# Main_autotest.net
KiCad netlist of a schematic drawn in EAGLE
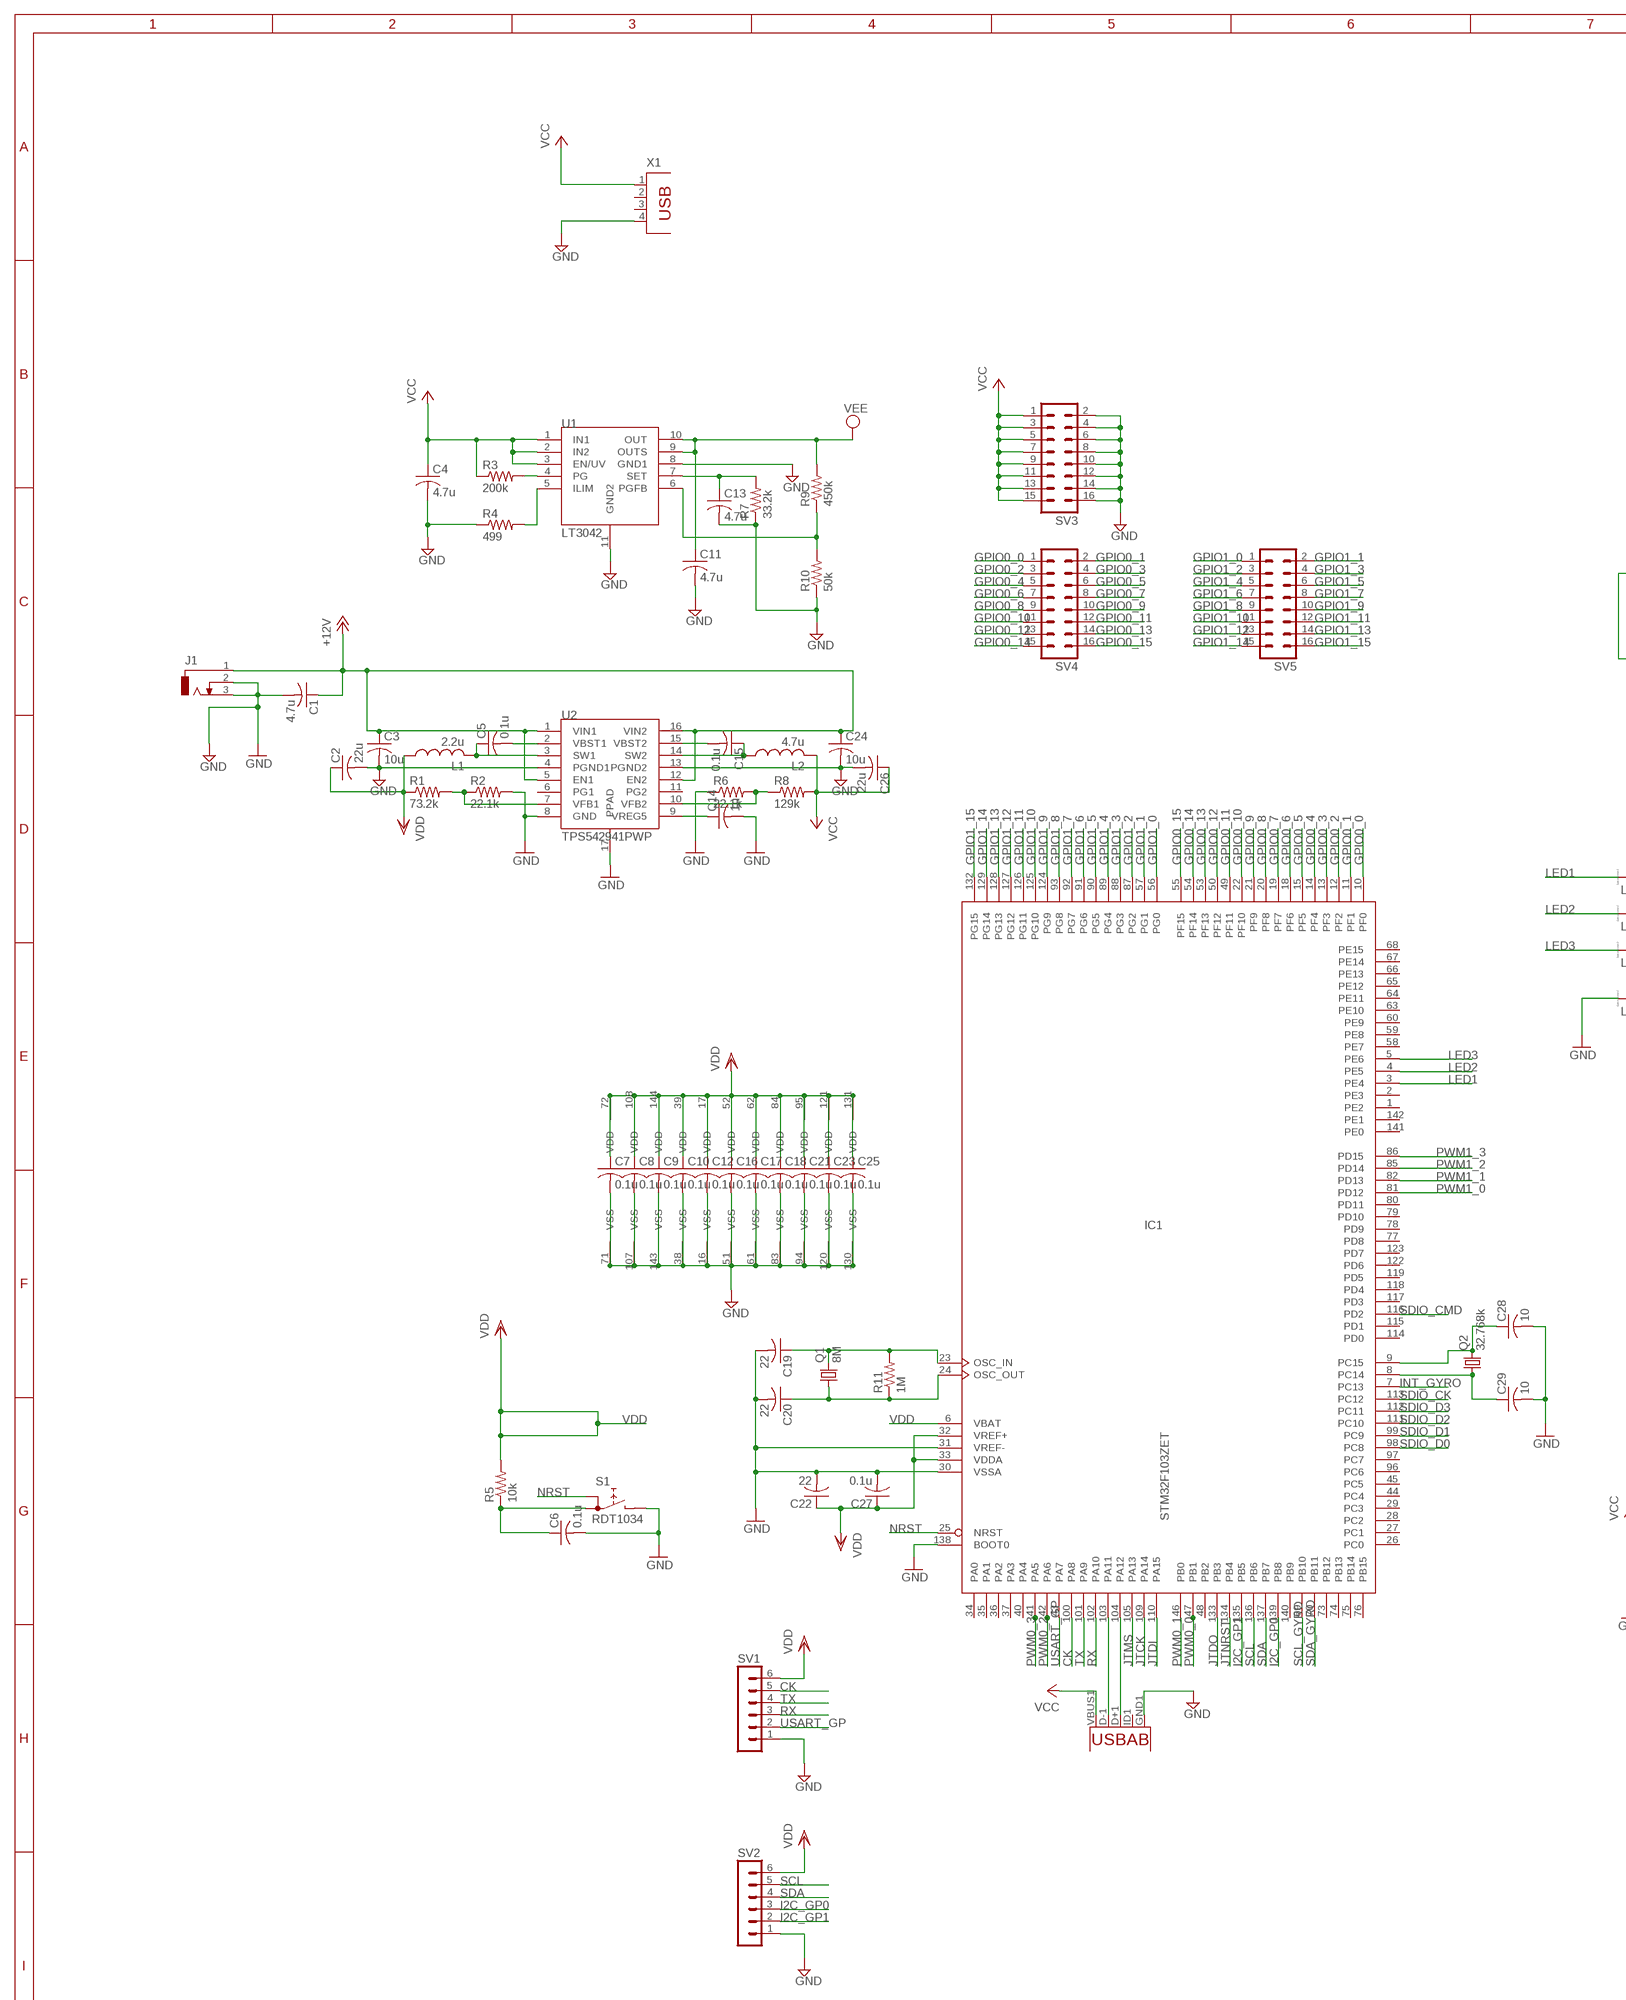
[diagram p0: schematic, sheet 1, part 1 of 2]
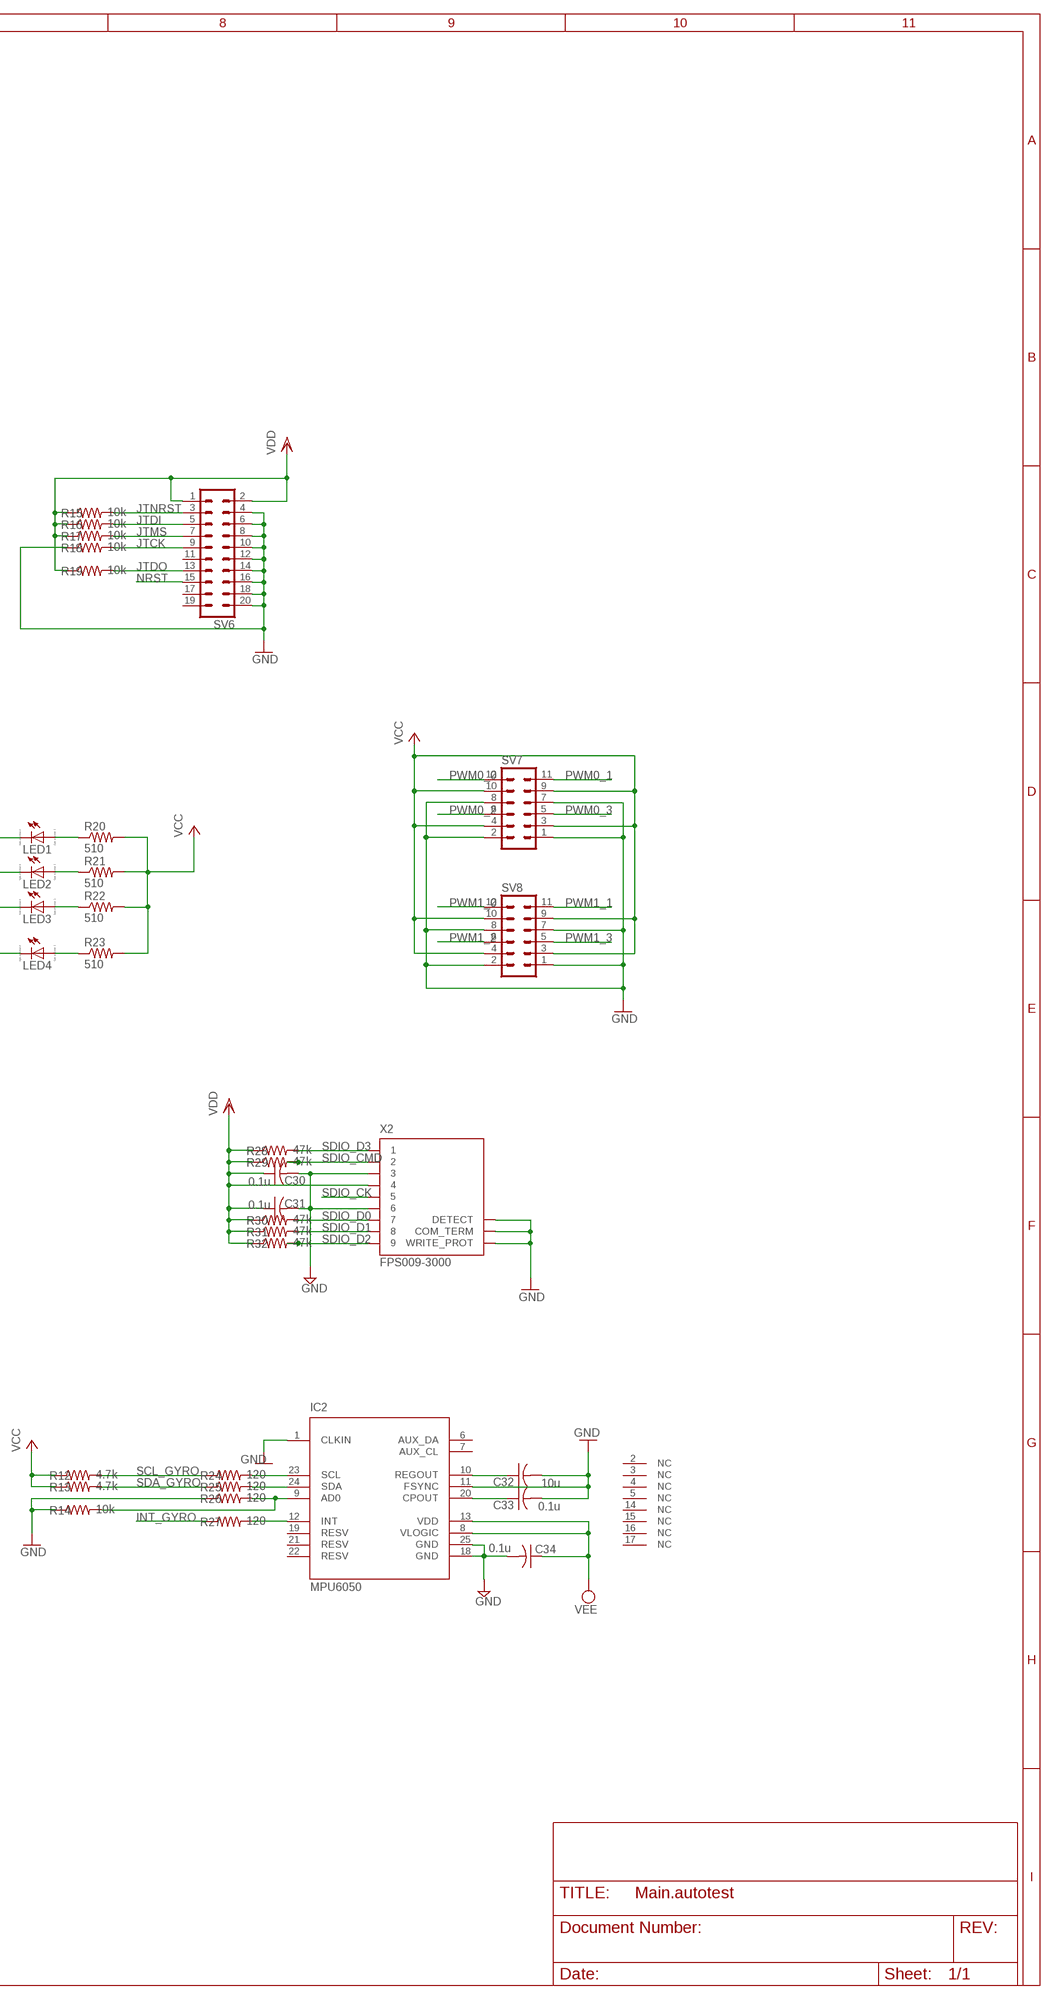
[diagram p1: schematic, sheet 1, part 2 of 2]

(export (version "E")
  (design (tool "Eeschema 10.0.6"))
  (components
    (comp (ref "C1")
      (value "4.7u")
      (footprint "eagle-import:C1206")
      (libsource (lib "eagle-import") (part "C-USC1206"))
    )
    (comp (ref "C2")
      (value "22u")
      (footprint "eagle-import:C0603")
      (libsource (lib "eagle-import") (part "C-USC0603"))
    )
    (comp (ref "C3")
      (value "10u")
      (footprint "eagle-import:C0603")
      (libsource (lib "eagle-import") (part "C-USC0603"))
    )
    (comp (ref "C4")
      (value "4.7u")
      (footprint "eagle-import:C0603")
      (libsource (lib "eagle-import") (part "C-USC0603"))
    )
    (comp (ref "C5")
      (value "0.1u")
      (footprint "eagle-import:C0603")
      (libsource (lib "eagle-import") (part "C-USC0603"))
    )
    (comp (ref "C6")
      (value "0.1u")
      (footprint "eagle-import:C0603")
      (libsource (lib "eagle-import") (part "C-USC0603"))
    )
    (comp (ref "C7")
      (value "0.1u")
      (footprint "eagle-import:C0603")
      (libsource (lib "eagle-import") (part "C-USC0603"))
    )
    (comp (ref "C8")
      (value "0.1u")
      (footprint "eagle-import:C0603")
      (libsource (lib "eagle-import") (part "C-USC0603"))
    )
    (comp (ref "C9")
      (value "0.1u")
      (footprint "eagle-import:C0603")
      (libsource (lib "eagle-import") (part "C-USC0603"))
    )
    (comp (ref "C10")
      (value "0.1u")
      (footprint "eagle-import:C0603")
      (libsource (lib "eagle-import") (part "C-USC0603"))
    )
    (comp (ref "C11")
      (value "4.7u")
      (footprint "eagle-import:C0603")
      (libsource (lib "eagle-import") (part "C-USC0603"))
    )
    (comp (ref "C12")
      (value "0.1u")
      (footprint "eagle-import:C0603")
      (libsource (lib "eagle-import") (part "C-USC0603"))
    )
    (comp (ref "C13")
      (value "4.7u")
      (footprint "eagle-import:C0603")
      (libsource (lib "eagle-import") (part "C-USC0603"))
    )
    (comp (ref "C14")
      (value "1u")
      (footprint "eagle-import:C0603")
      (libsource (lib "eagle-import") (part "C-USC0603"))
    )
    (comp (ref "C15")
      (value "0.1u")
      (footprint "eagle-import:C0603")
      (libsource (lib "eagle-import") (part "C-USC0603"))
    )
    (comp (ref "C16")
      (value "0.1u")
      (footprint "eagle-import:C0603")
      (libsource (lib "eagle-import") (part "C-USC0603"))
    )
    (comp (ref "C17")
      (value "0.1u")
      (footprint "eagle-import:C0603")
      (libsource (lib "eagle-import") (part "C-USC0603"))
    )
    (comp (ref "C18")
      (value "0.1u")
      (footprint "eagle-import:C0603")
      (libsource (lib "eagle-import") (part "C-USC0603"))
    )
    (comp (ref "C19")
      (value "22")
      (footprint "eagle-import:C0603")
      (libsource (lib "eagle-import") (part "C-USC0603"))
    )
    (comp (ref "C20")
      (value "22")
      (footprint "eagle-import:C0603")
      (libsource (lib "eagle-import") (part "C-USC0603"))
    )
    (comp (ref "C21")
      (value "0.1u")
      (footprint "eagle-import:C0603")
      (libsource (lib "eagle-import") (part "C-USC0603"))
    )
    (comp (ref "C22")
      (value "22")
      (footprint "eagle-import:C0603")
      (libsource (lib "eagle-import") (part "C-USC0603"))
    )
    (comp (ref "C23")
      (value "0.1u")
      (footprint "eagle-import:C0603")
      (libsource (lib "eagle-import") (part "C-USC0603"))
    )
    (comp (ref "C24")
      (value "10u")
      (footprint "eagle-import:C0603")
      (libsource (lib "eagle-import") (part "C-USC0603"))
    )
    (comp (ref "C25")
      (value "0.1u")
      (footprint "eagle-import:C0603")
      (libsource (lib "eagle-import") (part "C-USC0603"))
    )
    (comp (ref "C26")
      (value "22u")
      (footprint "eagle-import:C0603")
      (libsource (lib "eagle-import") (part "C-USC0603"))
    )
    (comp (ref "C27")
      (value "0.1u")
      (footprint "eagle-import:C0603")
      (libsource (lib "eagle-import") (part "C-USC0603"))
    )
    (comp (ref "C28")
      (value "10")
      (footprint "eagle-import:C0603")
      (libsource (lib "eagle-import") (part "C-USC0603"))
    )
    (comp (ref "C29")
      (value "10")
      (footprint "eagle-import:C0603")
      (libsource (lib "eagle-import") (part "C-USC0603"))
    )
    (comp (ref "C30")
      (value "0.1u")
      (footprint "eagle-import:C0603")
      (libsource (lib "eagle-import") (part "C-USC0603"))
    )
    (comp (ref "C31")
      (value "0.1u")
      (footprint "eagle-import:C0603")
      (libsource (lib "eagle-import") (part "C-USC0603"))
    )
    (comp (ref "C32")
      (value "10u")
      (footprint "eagle-import:C0603")
      (libsource (lib "eagle-import") (part "C-USC0603"))
    )
    (comp (ref "C33")
      (value "0.1u")
      (footprint "eagle-import:C0603")
      (libsource (lib "eagle-import") (part "C-USC0603"))
    )
    (comp (ref "C34")
      (value "0.1u")
      (footprint "eagle-import:C0603")
      (libsource (lib "eagle-import") (part "C-USC0603"))
    )
    (comp (ref "IC1")
      (value "STM32F103ZET")
      (footprint "eagle-import:LQFP144")
      (libsource (lib "eagle-import") (part "STM32F103ZTE"))
    )
    (comp (ref "IC2")
      (value "MPU6050")
      (footprint "eagle-import:QFN50P400X400X95-25T265X275N")
      (libsource (lib "eagle-import") (part "MPU6050"))
    )
    (comp (ref "J1")
      (value "DCJ0303")
      (footprint "eagle-import:DCJ0303")
      (libsource (lib "eagle-import") (part "DCJ0303"))
    )
    (comp (ref "L1")
      (value "2.2u")
      (footprint "eagle-import:L1812")
      (libsource (lib "eagle-import") (part "L-USL1812"))
    )
    (comp (ref "L2")
      (value "4.7u")
      (footprint "eagle-import:L1812")
      (libsource (lib "eagle-import") (part "L-USL1812"))
    )
    (comp (ref "LED1")
      (value "LED_E")
      (footprint "eagle-import:LED_1206")
      (libsource (lib "eagle-import") (part "LED_E"))
    )
    (comp (ref "LED2")
      (value "LED_E")
      (footprint "eagle-import:LED_1206")
      (libsource (lib "eagle-import") (part "LED_E"))
    )
    (comp (ref "LED3")
      (value "LED_E")
      (footprint "eagle-import:LED_1206")
      (libsource (lib "eagle-import") (part "LED_E"))
    )
    (comp (ref "LED4")
      (value "LED_E")
      (footprint "eagle-import:LED_1206")
      (libsource (lib "eagle-import") (part "LED_E"))
    )
    (comp (ref "Q1")
      (value "8M")
      (footprint "eagle-import:HC49UP")
      (libsource (lib "eagle-import") (part "CRYSTALHC49UP"))
    )
    (comp (ref "Q2")
      (value "32.768k")
      (footprint "eagle-import:HC49UP")
      (libsource (lib "eagle-import") (part "CRYSTALHC49UP"))
    )
    (comp (ref "R1")
      (value "73.2k")
      (footprint "eagle-import:R1206")
      (libsource (lib "eagle-import") (part "R-US_R1206"))
    )
    (comp (ref "R2")
      (value "22.1k")
      (footprint "eagle-import:R1206")
      (libsource (lib "eagle-import") (part "R-US_R1206"))
    )
    (comp (ref "R3")
      (value "200k")
      (footprint "eagle-import:R0603")
      (libsource (lib "eagle-import") (part "R-US_R0603"))
    )
    (comp (ref "R4")
      (value "499")
      (footprint "eagle-import:R0603")
      (libsource (lib "eagle-import") (part "R-US_R0603"))
    )
    (comp (ref "R5")
      (value "10k")
      (footprint "eagle-import:R0603")
      (libsource (lib "eagle-import") (part "R-US_R0603"))
    )
    (comp (ref "R6")
      (value "22.1k")
      (footprint "eagle-import:R1206")
      (libsource (lib "eagle-import") (part "R-US_R1206"))
    )
    (comp (ref "R7")
      (value "33.2k")
      (footprint "eagle-import:R0603")
      (libsource (lib "eagle-import") (part "R-US_R0603"))
    )
    (comp (ref "R8")
      (value "129k")
      (footprint "eagle-import:R1206")
      (libsource (lib "eagle-import") (part "R-US_R1206"))
    )
    (comp (ref "R9")
      (value "450k")
      (footprint "eagle-import:R0603")
      (libsource (lib "eagle-import") (part "R-US_R0603"))
    )
    (comp (ref "R10")
      (value "50k")
      (footprint "eagle-import:R0603")
      (libsource (lib "eagle-import") (part "R-US_R0603"))
    )
    (comp (ref "R11")
      (value "1M")
      (footprint "eagle-import:R0603")
      (libsource (lib "eagle-import") (part "R-US_R0603"))
    )
    (comp (ref "R12")
      (value "4.7k")
      (footprint "eagle-import:R0603")
      (libsource (lib "eagle-import") (part "R-US_R0603"))
    )
    (comp (ref "R13")
      (value "4.7k")
      (footprint "eagle-import:R0603")
      (libsource (lib "eagle-import") (part "R-US_R0603"))
    )
    (comp (ref "R14")
      (value "10k")
      (footprint "eagle-import:R0603")
      (libsource (lib "eagle-import") (part "R-US_R0603"))
    )
    (comp (ref "R15")
      (value "10k")
      (footprint "eagle-import:R0603")
      (libsource (lib "eagle-import") (part "resistor_R-US_R0603"))
    )
    (comp (ref "R16")
      (value "10k")
      (footprint "eagle-import:R0603")
      (libsource (lib "eagle-import") (part "resistor_R-US_R0603"))
    )
    (comp (ref "R17")
      (value "10k")
      (footprint "eagle-import:R0603")
      (libsource (lib "eagle-import") (part "resistor_R-US_R0603"))
    )
    (comp (ref "R18")
      (value "10k")
      (footprint "eagle-import:R0603")
      (libsource (lib "eagle-import") (part "resistor_R-US_R0603"))
    )
    (comp (ref "R19")
      (value "10k")
      (footprint "eagle-import:R0603")
      (libsource (lib "eagle-import") (part "resistor_R-US_R0603"))
    )
    (comp (ref "R20")
      (value "510")
      (footprint "eagle-import:R0603")
      (libsource (lib "eagle-import") (part "R-US_R0603"))
    )
    (comp (ref "R21")
      (value "510")
      (footprint "eagle-import:R0603")
      (libsource (lib "eagle-import") (part "R-US_R0603"))
    )
    (comp (ref "R22")
      (value "510")
      (footprint "eagle-import:R0603")
      (libsource (lib "eagle-import") (part "R-US_R0603"))
    )
    (comp (ref "R23")
      (value "510")
      (footprint "eagle-import:R0603")
      (libsource (lib "eagle-import") (part "R-US_R0603"))
    )
    (comp (ref "R24")
      (value "120")
      (footprint "eagle-import:R0603")
      (libsource (lib "eagle-import") (part "R-US_R0603"))
    )
    (comp (ref "R25")
      (value "120")
      (footprint "eagle-import:R0603")
      (libsource (lib "eagle-import") (part "R-US_R0603"))
    )
    (comp (ref "R26")
      (value "120")
      (footprint "eagle-import:R0603")
      (libsource (lib "eagle-import") (part "R-US_R0603"))
    )
    (comp (ref "R27")
      (value "120")
      (footprint "eagle-import:R0603")
      (libsource (lib "eagle-import") (part "R-US_R0603"))
    )
    (comp (ref "R28")
      (value "47k")
      (footprint "eagle-import:R0603")
      (libsource (lib "eagle-import") (part "R-US_R0603"))
    )
    (comp (ref "R29")
      (value "47k")
      (footprint "eagle-import:R0603")
      (libsource (lib "eagle-import") (part "R-US_R0603"))
    )
    (comp (ref "R30")
      (value "47k")
      (footprint "eagle-import:R0603")
      (libsource (lib "eagle-import") (part "R-US_R0603"))
    )
    (comp (ref "R31")
      (value "47k")
      (footprint "eagle-import:R0603")
      (libsource (lib "eagle-import") (part "R-US_R0603"))
    )
    (comp (ref "R32")
      (value "47k")
      (footprint "eagle-import:R0603")
      (libsource (lib "eagle-import") (part "R-US_R0603"))
    )
    (comp (ref "S1")
      (value "RDT1034")
      (footprint "eagle-import:RDT1034")
      (libsource (lib "eagle-import") (part "RDT1034"))
    )
    (comp (ref "SV1")
      (value "MA06-1")
      (footprint "eagle-import:MA06-1")
      (libsource (lib "eagle-import") (part "MA06-1"))
    )
    (comp (ref "SV2")
      (value "MA06-1")
      (footprint "eagle-import:MA06-1")
      (libsource (lib "eagle-import") (part "MA06-1"))
    )
    (comp (ref "SV3")
      (value "MA08-2")
      (footprint "eagle-import:MA08-2")
      (libsource (lib "eagle-import") (part "MA08-2"))
    )
    (comp (ref "SV4")
      (value "MA08-2")
      (footprint "eagle-import:MA08-2")
      (libsource (lib "eagle-import") (part "MA08-2"))
    )
    (comp (ref "SV5")
      (value "MA08-2")
      (footprint "eagle-import:MA08-2")
      (libsource (lib "eagle-import") (part "MA08-2"))
    )
    (comp (ref "SV6")
      (value "MA10-2")
      (footprint "eagle-import:MA10-2")
      (libsource (lib "eagle-import") (part "MA10-2"))
    )
    (comp (ref "SV7")
      (value "MA06-2")
      (footprint "eagle-import:MA06-2")
      (libsource (lib "eagle-import") (part "MA06-2"))
    )
    (comp (ref "SV8")
      (value "MA06-2")
      (footprint "eagle-import:MA06-2")
      (libsource (lib "eagle-import") (part "MA06-2"))
    )
    (comp (ref "U1")
      (value "LT3042")
      (footprint "eagle-import:LT3042")
      (libsource (lib "eagle-import") (part "LT3042"))
    )
    (comp (ref "U2")
      (value "TPS542941PWP")
      (footprint "eagle-import:HTSSOP16")
      (libsource (lib "eagle-import") (part "TPS542941PWP"))
    )
    (comp (ref "U3")
      (value "USB\"\"")
      (footprint "eagle-import:USB-MICRO-SMD")
      (libsource (lib "eagle-import") (part "USB{dblquote}{dblquote}"))
    )
    (comp (ref "X1")
      (value "PN87520")
      (footprint "eagle-import:PN87520")
      (libsource (lib "eagle-import") (part "PN87520"))
    )
    (comp (ref "X2")
      (value "FPS009-3000")
      (footprint "eagle-import:FPS009-3000")
      (libsource (lib "eagle-import") (part "FPS009-3000"))
    )
  )
  (nets
    (net (code "1") (name "+12V") (class "Default")
      (node (ref "C1") (pin "1") (pinfunction "1_1") (pintype "passive"))
      (node (ref "C24") (pin "1") (pinfunction "1_1") (pintype "passive"))
      (node (ref "C3") (pin "1") (pinfunction "1_1") (pintype "passive"))
      (node (ref "J1") (pin "1") (pinfunction "1_1") (pintype "passive"))
      (node (ref "U2") (pin "1") (pinfunction "VIN1_1") (pintype "input"))
      (node (ref "U2") (pin "12") (pinfunction "EN2_12") (pintype "input"))
      (node (ref "U2") (pin "16") (pinfunction "VIN2_16") (pintype "input"))
      (node (ref "U2") (pin "5") (pinfunction "EN1_5") (pintype "input"))
    )
    (net (code "2") (name "/CK") (class "Default")
      (node (ref "IC1") (pin "100") (pinfunction "PA8_100") (pintype "bidirectional"))
      (node (ref "SV1") (pin "5") (pinfunction "5_5") (pintype "passive"))
    )
    (net (code "3") (name "/GPIO0_0") (class "Default")
      (node (ref "IC1") (pin "10") (pinfunction "PF0_10") (pintype "bidirectional"))
      (node (ref "SV4") (pin "1") (pinfunction "1_1") (pintype "passive"))
    )
    (net (code "4") (name "/GPIO0_1") (class "Default")
      (node (ref "IC1") (pin "11") (pinfunction "PF1_11") (pintype "bidirectional"))
      (node (ref "SV4") (pin "2") (pinfunction "2_2") (pintype "passive"))
    )
    (net (code "5") (name "/GPIO0_2") (class "Default")
      (node (ref "IC1") (pin "12") (pinfunction "PF2_12") (pintype "bidirectional"))
      (node (ref "SV4") (pin "3") (pinfunction "3_3") (pintype "passive"))
    )
    (net (code "6") (name "/GPIO0_3") (class "Default")
      (node (ref "IC1") (pin "13") (pinfunction "PF3_13") (pintype "bidirectional"))
      (node (ref "SV4") (pin "4") (pinfunction "4_4") (pintype "passive"))
    )
    (net (code "7") (name "/GPIO0_4") (class "Default")
      (node (ref "IC1") (pin "14") (pinfunction "PF4_14") (pintype "bidirectional"))
      (node (ref "SV4") (pin "5") (pinfunction "5_5") (pintype "passive"))
    )
    (net (code "8") (name "/GPIO0_5") (class "Default")
      (node (ref "IC1") (pin "15") (pinfunction "PF5_15") (pintype "bidirectional"))
      (node (ref "SV4") (pin "6") (pinfunction "6_6") (pintype "passive"))
    )
    (net (code "9") (name "/GPIO0_6") (class "Default")
      (node (ref "IC1") (pin "18") (pinfunction "PF6_18") (pintype "bidirectional"))
      (node (ref "SV4") (pin "7") (pinfunction "7_7") (pintype "passive"))
    )
    (net (code "10") (name "/GPIO0_7") (class "Default")
      (node (ref "IC1") (pin "19") (pinfunction "PF7_19") (pintype "bidirectional"))
      (node (ref "SV4") (pin "8") (pinfunction "8_8") (pintype "passive"))
    )
    (net (code "11") (name "/GPIO0_8") (class "Default")
      (node (ref "IC1") (pin "20") (pinfunction "PF8_20") (pintype "bidirectional"))
      (node (ref "SV4") (pin "9") (pinfunction "9_9") (pintype "passive"))
    )
    (net (code "12") (name "/GPIO0_9") (class "Default")
      (node (ref "IC1") (pin "21") (pinfunction "PF9_21") (pintype "bidirectional"))
      (node (ref "SV4") (pin "10") (pinfunction "10_10") (pintype "passive"))
    )
    (net (code "13") (name "/GPIO0_10") (class "Default")
      (node (ref "IC1") (pin "22") (pinfunction "PF10_22") (pintype "bidirectional"))
      (node (ref "SV4") (pin "11") (pinfunction "11_11") (pintype "passive"))
    )
    (net (code "14") (name "/GPIO0_11") (class "Default")
      (node (ref "IC1") (pin "49") (pinfunction "PF11_49") (pintype "bidirectional"))
      (node (ref "SV4") (pin "12") (pinfunction "12_12") (pintype "passive"))
    )
    (net (code "15") (name "/GPIO0_12") (class "Default")
      (node (ref "IC1") (pin "50") (pinfunction "PF12_50") (pintype "bidirectional"))
      (node (ref "SV4") (pin "13") (pinfunction "13_13") (pintype "passive"))
    )
    (net (code "16") (name "/GPIO0_13") (class "Default")
      (node (ref "IC1") (pin "53") (pinfunction "PF13_53") (pintype "bidirectional"))
      (node (ref "SV4") (pin "14") (pinfunction "14_14") (pintype "passive"))
    )
    (net (code "17") (name "/GPIO0_14") (class "Default")
      (node (ref "IC1") (pin "54") (pinfunction "PF14_54") (pintype "bidirectional"))
      (node (ref "SV4") (pin "15") (pinfunction "15_15") (pintype "passive"))
    )
    (net (code "18") (name "/GPIO0_15") (class "Default")
      (node (ref "IC1") (pin "55") (pinfunction "PF15_55") (pintype "bidirectional"))
      (node (ref "SV4") (pin "16") (pinfunction "16_16") (pintype "passive"))
    )
    (net (code "19") (name "/GPIO1_0") (class "Default")
      (node (ref "IC1") (pin "56") (pinfunction "PG0_56") (pintype "bidirectional"))
      (node (ref "SV5") (pin "1") (pinfunction "1_1") (pintype "passive"))
    )
    (net (code "20") (name "/GPIO1_1") (class "Default")
      (node (ref "IC1") (pin "57") (pinfunction "PG1_57") (pintype "bidirectional"))
      (node (ref "SV5") (pin "2") (pinfunction "2_2") (pintype "passive"))
    )
    (net (code "21") (name "/GPIO1_2") (class "Default")
      (node (ref "IC1") (pin "87") (pinfunction "PG2_87") (pintype "bidirectional"))
      (node (ref "SV5") (pin "3") (pinfunction "3_3") (pintype "passive"))
    )
    (net (code "22") (name "/GPIO1_3") (class "Default")
      (node (ref "IC1") (pin "88") (pinfunction "PG3_88") (pintype "bidirectional"))
      (node (ref "SV5") (pin "4") (pinfunction "4_4") (pintype "passive"))
    )
    (net (code "23") (name "/GPIO1_4") (class "Default")
      (node (ref "IC1") (pin "89") (pinfunction "PG4_89") (pintype "bidirectional"))
      (node (ref "SV5") (pin "5") (pinfunction "5_5") (pintype "passive"))
    )
    (net (code "24") (name "/GPIO1_5") (class "Default")
      (node (ref "IC1") (pin "90") (pinfunction "PG5_90") (pintype "bidirectional"))
      (node (ref "SV5") (pin "6") (pinfunction "6_6") (pintype "passive"))
    )
    (net (code "25") (name "/GPIO1_6") (class "Default")
      (node (ref "IC1") (pin "91") (pinfunction "PG6_91") (pintype "bidirectional"))
      (node (ref "SV5") (pin "7") (pinfunction "7_7") (pintype "passive"))
    )
    (net (code "26") (name "/GPIO1_7") (class "Default")
      (node (ref "IC1") (pin "92") (pinfunction "PG7_92") (pintype "bidirectional"))
      (node (ref "SV5") (pin "8") (pinfunction "8_8") (pintype "passive"))
    )
    (net (code "27") (name "/GPIO1_8") (class "Default")
      (node (ref "IC1") (pin "93") (pinfunction "PG8_93") (pintype "bidirectional"))
      (node (ref "SV5") (pin "9") (pinfunction "9_9") (pintype "passive"))
    )
    (net (code "28") (name "/GPIO1_9") (class "Default")
      (node (ref "IC1") (pin "124") (pinfunction "PG9_124") (pintype "bidirectional"))
      (node (ref "SV5") (pin "10") (pinfunction "10_10") (pintype "passive"))
    )
    (net (code "29") (name "/GPIO1_10") (class "Default")
      (node (ref "IC1") (pin "125") (pinfunction "PG10_125") (pintype "bidirectional"))
      (node (ref "SV5") (pin "11") (pinfunction "11_11") (pintype "passive"))
    )
    (net (code "30") (name "/GPIO1_11") (class "Default")
      (node (ref "IC1") (pin "126") (pinfunction "PG11_126") (pintype "bidirectional"))
      (node (ref "SV5") (pin "12") (pinfunction "12_12") (pintype "passive"))
    )
    (net (code "31") (name "/GPIO1_12") (class "Default")
      (node (ref "IC1") (pin "127") (pinfunction "PG12_127") (pintype "bidirectional"))
      (node (ref "SV5") (pin "13") (pinfunction "13_13") (pintype "passive"))
    )
    (net (code "32") (name "/GPIO1_13") (class "Default")
      (node (ref "IC1") (pin "128") (pinfunction "PG13_128") (pintype "bidirectional"))
      (node (ref "SV5") (pin "14") (pinfunction "14_14") (pintype "passive"))
    )
    (net (code "33") (name "/GPIO1_14") (class "Default")
      (node (ref "IC1") (pin "129") (pinfunction "PG14_129") (pintype "bidirectional"))
      (node (ref "SV5") (pin "15") (pinfunction "15_15") (pintype "passive"))
    )
    (net (code "34") (name "/GPIO1_15") (class "Default")
      (node (ref "IC1") (pin "132") (pinfunction "PG15_132") (pintype "bidirectional"))
      (node (ref "SV5") (pin "16") (pinfunction "16_16") (pintype "passive"))
    )
    (net (code "35") (name "/I2C_GP0") (class "Default")
      (node (ref "IC1") (pin "139") (pinfunction "PB8_139") (pintype "bidirectional"))
      (node (ref "SV2") (pin "3") (pinfunction "3_3") (pintype "passive"))
    )
    (net (code "36") (name "/I2C_GP1") (class "Default")
      (node (ref "IC1") (pin "135") (pinfunction "PB5_135") (pintype "bidirectional"))
      (node (ref "SV2") (pin "2") (pinfunction "2_2") (pintype "passive"))
    )
    (net (code "37") (name "/INT_GYRO") (class "Default")
      (node (ref "IC1") (pin "7") (pinfunction "PC13_7") (pintype "bidirectional"))
      (node (ref "R27") (pin "1") (pinfunction "1_1") (pintype "passive"))
    )
    (net (code "38") (name "/JTCK") (class "Default")
      (node (ref "IC1") (pin "109") (pinfunction "PA14_109") (pintype "bidirectional"))
      (node (ref "R18") (pin "2") (pinfunction "2_2") (pintype "passive"))
      (node (ref "SV6") (pin "9") (pinfunction "9_9") (pintype "passive"))
    )
    (net (code "39") (name "/JTDI") (class "Default")
      (node (ref "IC1") (pin "110") (pinfunction "PA15_110") (pintype "bidirectional"))
      (node (ref "R16") (pin "2") (pinfunction "2_2") (pintype "passive"))
      (node (ref "SV6") (pin "5") (pinfunction "5_5") (pintype "passive"))
    )
    (net (code "40") (name "/JTDO") (class "Default")
      (node (ref "IC1") (pin "133") (pinfunction "PB3_133") (pintype "bidirectional"))
      (node (ref "R19") (pin "2") (pinfunction "2_2") (pintype "passive"))
      (node (ref "SV6") (pin "13") (pinfunction "13_13") (pintype "passive"))
    )
    (net (code "41") (name "/JTMS") (class "Default")
      (node (ref "IC1") (pin "105") (pinfunction "PA13_105") (pintype "bidirectional"))
      (node (ref "R17") (pin "2") (pinfunction "2_2") (pintype "passive"))
      (node (ref "SV6") (pin "7") (pinfunction "7_7") (pintype "passive"))
    )
    (net (code "42") (name "/JTNRST") (class "Default")
      (node (ref "IC1") (pin "134") (pinfunction "PB4_134") (pintype "bidirectional"))
      (node (ref "R15") (pin "2") (pinfunction "2_2") (pintype "passive"))
      (node (ref "SV6") (pin "3") (pinfunction "3_3") (pintype "passive"))
    )
    (net (code "43") (name "/LED1") (class "Default")
      (node (ref "IC1") (pin "3") (pinfunction "PE4_3") (pintype "bidirectional"))
      (node (ref "LED1") (pin "C") (pinfunction "C_C") (pintype "passive"))
    )
    (net (code "44") (name "/LED2") (class "Default")
      (node (ref "IC1") (pin "4") (pinfunction "PE5_4") (pintype "bidirectional"))
      (node (ref "LED2") (pin "C") (pinfunction "C_C") (pintype "passive"))
    )
    (net (code "45") (name "/LED3") (class "Default")
      (node (ref "IC1") (pin "5") (pinfunction "PE6_5") (pintype "bidirectional"))
      (node (ref "LED3") (pin "C") (pinfunction "C_C") (pintype "passive"))
    )
    (net (code "46") (name "/NRST") (class "Default")
      (node (ref "IC1") (pin "25") (pinfunction "NRST_25") (pintype "bidirectional"))
      (node (ref "S1") (pin "A") (pinfunction "A_A") (pintype "passive"))
      (node (ref "SV6") (pin "15") (pinfunction "15_15") (pintype "passive"))
    )
    (net (code "47") (name "/PWM0_0") (class "Default")
      (node (ref "IC1") (pin "47") (pinfunction "PB1_47") (pintype "bidirectional"))
      (node (ref "SV7") (pin "12") (pinfunction "12_12") (pintype "passive"))
    )
    (net (code "48") (name "/PWM0_1") (class "Default")
      (node (ref "IC1") (pin "46") (pinfunction "PB0_46") (pintype "bidirectional"))
      (node (ref "SV7") (pin "11") (pinfunction "11_11") (pintype "passive"))
    )
    (net (code "49") (name "/PWM0_2") (class "Default")
      (node (ref "IC1") (pin "42") (pinfunction "PA6_42") (pintype "bidirectional"))
      (node (ref "SV7") (pin "6") (pinfunction "6_6") (pintype "passive"))
    )
    (net (code "50") (name "/PWM0_3") (class "Default")
      (node (ref "IC1") (pin "41") (pinfunction "PA5_41") (pintype "bidirectional"))
      (node (ref "SV7") (pin "5") (pinfunction "5_5") (pintype "passive"))
    )
    (net (code "51") (name "/PWM1_0") (class "Default")
      (node (ref "IC1") (pin "81") (pinfunction "PD12_81") (pintype "bidirectional"))
      (node (ref "SV8") (pin "12") (pinfunction "12_12") (pintype "passive"))
    )
    (net (code "52") (name "/PWM1_1") (class "Default")
      (node (ref "IC1") (pin "82") (pinfunction "PD13_82") (pintype "bidirectional"))
      (node (ref "SV8") (pin "11") (pinfunction "11_11") (pintype "passive"))
    )
    (net (code "53") (name "/PWM1_2") (class "Default")
      (node (ref "IC1") (pin "85") (pinfunction "PD14_85") (pintype "bidirectional"))
      (node (ref "SV8") (pin "6") (pinfunction "6_6") (pintype "passive"))
    )
    (net (code "54") (name "/PWM1_3") (class "Default")
      (node (ref "IC1") (pin "86") (pinfunction "PD15_86") (pintype "bidirectional"))
      (node (ref "SV8") (pin "5") (pinfunction "5_5") (pintype "passive"))
    )
    (net (code "55") (name "/RX") (class "Default")
      (node (ref "IC1") (pin "102") (pinfunction "PA10_102") (pintype "bidirectional"))
      (node (ref "SV1") (pin "3") (pinfunction "3_3") (pintype "passive"))
    )
    (net (code "56") (name "/SCL") (class "Default")
      (node (ref "IC1") (pin "136") (pinfunction "PB6_136") (pintype "bidirectional"))
      (node (ref "SV2") (pin "5") (pinfunction "5_5") (pintype "passive"))
    )
    (net (code "57") (name "/SCL_GYRO") (class "Default")
      (node (ref "IC1") (pin "69") (pinfunction "PB10_69") (pintype "bidirectional"))
      (node (ref "R12") (pin "2") (pinfunction "2_2") (pintype "passive"))
      (node (ref "R24") (pin "1") (pinfunction "1_1") (pintype "passive"))
    )
    (net (code "58") (name "/SDA") (class "Default")
      (node (ref "IC1") (pin "137") (pinfunction "PB7_137") (pintype "bidirectional"))
      (node (ref "SV2") (pin "4") (pinfunction "4_4") (pintype "passive"))
    )
    (net (code "59") (name "/SDA_GYRO") (class "Default")
      (node (ref "IC1") (pin "70") (pinfunction "PB11_70") (pintype "bidirectional"))
      (node (ref "R13") (pin "2") (pinfunction "2_2") (pintype "passive"))
      (node (ref "R25") (pin "1") (pinfunction "1_1") (pintype "passive"))
    )
    (net (code "60") (name "/SDIO_CK") (class "Default")
      (node (ref "IC1") (pin "113") (pinfunction "PC12_113") (pintype "bidirectional"))
      (node (ref "X2") (pin "5") (pinfunction "5_5") (pintype "input"))
    )
    (net (code "61") (name "/SDIO_CMD") (class "Default")
      (node (ref "IC1") (pin "116") (pinfunction "PD2_116") (pintype "bidirectional"))
      (node (ref "R29") (pin "2") (pinfunction "2_2") (pintype "passive"))
      (node (ref "X2") (pin "2") (pinfunction "2_2") (pintype "input"))
    )
    (net (code "62") (name "/SDIO_D0") (class "Default")
      (node (ref "IC1") (pin "98") (pinfunction "PC8_98") (pintype "bidirectional"))
      (node (ref "R30") (pin "2") (pinfunction "2_2") (pintype "passive"))
      (node (ref "X2") (pin "7") (pinfunction "7_7") (pintype "input"))
    )
    (net (code "63") (name "/SDIO_D1") (class "Default")
      (node (ref "IC1") (pin "99") (pinfunction "PC9_99") (pintype "bidirectional"))
      (node (ref "R31") (pin "2") (pinfunction "2_2") (pintype "passive"))
      (node (ref "X2") (pin "8") (pinfunction "8_8") (pintype "input"))
    )
    (net (code "64") (name "/SDIO_D2") (class "Default")
      (node (ref "IC1") (pin "111") (pinfunction "PC10_111") (pintype "bidirectional"))
      (node (ref "R32") (pin "2") (pinfunction "2_2") (pintype "passive"))
      (node (ref "X2") (pin "9") (pinfunction "9_9") (pintype "input"))
    )
    (net (code "65") (name "/SDIO_D3") (class "Default")
      (node (ref "IC1") (pin "112") (pinfunction "PC11_112") (pintype "bidirectional"))
      (node (ref "R28") (pin "2") (pinfunction "2_2") (pintype "passive"))
      (node (ref "X2") (pin "1") (pinfunction "1_1") (pintype "input"))
    )
    (net (code "66") (name "/TX") (class "Default")
      (node (ref "IC1") (pin "101") (pinfunction "PA9_101") (pintype "bidirectional"))
      (node (ref "SV1") (pin "4") (pinfunction "4_4") (pintype "passive"))
    )
    (net (code "67") (name "/USART_GP") (class "Default")
      (node (ref "IC1") (pin "43") (pinfunction "PA7_43") (pintype "bidirectional"))
      (node (ref "SV1") (pin "2") (pinfunction "2_2") (pintype "passive"))
    )
    (net (code "68") (name "GND") (class "Default")
      (node (ref "C1") (pin "2") (pinfunction "2_2") (pintype "passive"))
      (node (ref "C10") (pin "2") (pinfunction "2_2") (pintype "passive"))
      (node (ref "C11") (pin "2") (pinfunction "2_2") (pintype "passive"))
      (node (ref "C12") (pin "2") (pinfunction "2_2") (pintype "passive"))
      (node (ref "C13") (pin "2") (pinfunction "2_2") (pintype "passive"))
      (node (ref "C14") (pin "2") (pinfunction "2_2") (pintype "passive"))
      (node (ref "C16") (pin "2") (pinfunction "2_2") (pintype "passive"))
      (node (ref "C17") (pin "2") (pinfunction "2_2") (pintype "passive"))
      (node (ref "C18") (pin "2") (pinfunction "2_2") (pintype "passive"))
      (node (ref "C19") (pin "2") (pinfunction "2_2") (pintype "passive"))
      (node (ref "C2") (pin "2") (pinfunction "2_2") (pintype "passive"))
      (node (ref "C20") (pin "2") (pinfunction "2_2") (pintype "passive"))
      (node (ref "C21") (pin "2") (pinfunction "2_2") (pintype "passive"))
      (node (ref "C22") (pin "2") (pinfunction "2_2") (pintype "passive"))
      (node (ref "C23") (pin "2") (pinfunction "2_2") (pintype "passive"))
      (node (ref "C24") (pin "2") (pinfunction "2_2") (pintype "passive"))
      (node (ref "C25") (pin "2") (pinfunction "2_2") (pintype "passive"))
      (node (ref "C26") (pin "2") (pinfunction "2_2") (pintype "passive"))
      (node (ref "C27") (pin "2") (pinfunction "2_2") (pintype "passive"))
      (node (ref "C28") (pin "2") (pinfunction "2_2") (pintype "passive"))
      (node (ref "C29") (pin "2") (pinfunction "2_2") (pintype "passive"))
      (node (ref "C3") (pin "2") (pinfunction "2_2") (pintype "passive"))
      (node (ref "C30") (pin "2") (pinfunction "2_2") (pintype "passive"))
      (node (ref "C31") (pin "2") (pinfunction "2_2") (pintype "passive"))
      (node (ref "C32") (pin "2") (pinfunction "2_2") (pintype "passive"))
      (node (ref "C33") (pin "2") (pinfunction "2_2") (pintype "passive"))
      (node (ref "C34") (pin "2") (pinfunction "2_2") (pintype "passive"))
      (node (ref "C4") (pin "2") (pinfunction "2_2") (pintype "passive"))
      (node (ref "C6") (pin "2") (pinfunction "2_2") (pintype "passive"))
      (node (ref "C7") (pin "2") (pinfunction "2_2") (pintype "passive"))
      (node (ref "C8") (pin "2") (pinfunction "2_2") (pintype "passive"))
      (node (ref "C9") (pin "2") (pinfunction "2_2") (pintype "passive"))
      (node (ref "IC1") (pin "107") (pinfunction "VSS_107") (pintype "power_in"))
      (node (ref "IC1") (pin "120") (pinfunction "VSS_120") (pintype "power_in"))
      (node (ref "IC1") (pin "130") (pinfunction "VSS_130") (pintype "power_in"))
      (node (ref "IC1") (pin "138") (pinfunction "BOOT0_138") (pintype "input"))
      (node (ref "IC1") (pin "143") (pinfunction "VSS_143") (pintype "power_in"))
      (node (ref "IC1") (pin "16") (pinfunction "VSS_16") (pintype "power_in"))
      (node (ref "IC1") (pin "30") (pinfunction "VSSA_30") (pintype "power_in"))
      (node (ref "IC1") (pin "31") (pinfunction "VREF-_31") (pintype "power_in"))
      (node (ref "IC1") (pin "38") (pinfunction "VSS_38") (pintype "power_in"))
      (node (ref "IC1") (pin "51") (pinfunction "VSS_51") (pintype "power_in"))
      (node (ref "IC1") (pin "61") (pinfunction "VSS_61") (pintype "power_in"))
      (node (ref "IC1") (pin "71") (pinfunction "VSS_71") (pintype "power_in"))
      (node (ref "IC1") (pin "83") (pinfunction "VSS_83") (pintype "power_in"))
      (node (ref "IC1") (pin "94") (pinfunction "VSS_94") (pintype "power_in"))
      (node (ref "IC2") (pin "1") (pinfunction "CLKIN_1") (pintype "input"))
      (node (ref "IC2") (pin "11") (pinfunction "FSYNC_11") (pintype "input"))
      (node (ref "IC2") (pin "18") (pinfunction "GND_18") (pintype "power_in"))
      (node (ref "IC2") (pin "25") (pinfunction "GND_25") (pintype "power_in"))
      (node (ref "J1") (pin "2") (pinfunction "2_2") (pintype "passive"))
      (node (ref "J1") (pin "3") (pinfunction "3_3") (pintype "passive"))
      (node (ref "LED4") (pin "C") (pinfunction "C_C") (pintype "passive"))
      (node (ref "R10") (pin "1") (pinfunction "1_1") (pintype "passive"))
      (node (ref "R14") (pin "1") (pinfunction "1_1") (pintype "passive"))
      (node (ref "R18") (pin "1") (pinfunction "1_1") (pintype "passive"))
      (node (ref "R2") (pin "2") (pinfunction "2_2") (pintype "passive"))
      (node (ref "R26") (pin "1") (pinfunction "1_1") (pintype "passive"))
      (node (ref "R4") (pin "1") (pinfunction "1_1") (pintype "passive"))
      (node (ref "R6") (pin "1") (pinfunction "1_1") (pintype "passive"))
      (node (ref "R7") (pin "1") (pinfunction "1_1") (pintype "passive"))
      (node (ref "S1") (pin "B") (pinfunction "B_B") (pintype "passive"))
      (node (ref "SV1") (pin "1") (pinfunction "1_1") (pintype "passive"))
      (node (ref "SV2") (pin "1") (pinfunction "1_1") (pintype "passive"))
      (node (ref "SV3") (pin "10") (pinfunction "10_10") (pintype "passive"))
      (node (ref "SV3") (pin "12") (pinfunction "12_12") (pintype "passive"))
      (node (ref "SV3") (pin "14") (pinfunction "14_14") (pintype "passive"))
      (node (ref "SV3") (pin "16") (pinfunction "16_16") (pintype "passive"))
      (node (ref "SV3") (pin "2") (pinfunction "2_2") (pintype "passive"))
      (node (ref "SV3") (pin "4") (pinfunction "4_4") (pintype "passive"))
      (node (ref "SV3") (pin "6") (pinfunction "6_6") (pintype "passive"))
      (node (ref "SV3") (pin "8") (pinfunction "8_8") (pintype "passive"))
      (node (ref "SV6") (pin "10") (pinfunction "10_10") (pintype "passive"))
      (node (ref "SV6") (pin "12") (pinfunction "12_12") (pintype "passive"))
      (node (ref "SV6") (pin "14") (pinfunction "14_14") (pintype "passive"))
      (node (ref "SV6") (pin "16") (pinfunction "16_16") (pintype "passive"))
      (node (ref "SV6") (pin "18") (pinfunction "18_18") (pintype "passive"))
      (node (ref "SV6") (pin "20") (pinfunction "20_20") (pintype "passive"))
      (node (ref "SV6") (pin "4") (pinfunction "4_4") (pintype "passive"))
      (node (ref "SV6") (pin "6") (pinfunction "6_6") (pintype "passive"))
      (node (ref "SV6") (pin "8") (pinfunction "8_8") (pintype "passive"))
      (node (ref "SV7") (pin "1") (pinfunction "1_1") (pintype "passive"))
      (node (ref "SV7") (pin "2") (pinfunction "2_2") (pintype "passive"))
      (node (ref "SV7") (pin "7") (pinfunction "7_7") (pintype "passive"))
      (node (ref "SV7") (pin "8") (pinfunction "8_8") (pintype "passive"))
      (node (ref "SV8") (pin "1") (pinfunction "1_1") (pintype "passive"))
      (node (ref "SV8") (pin "2") (pinfunction "2_2") (pintype "passive"))
      (node (ref "SV8") (pin "7") (pinfunction "7_7") (pintype "passive"))
      (node (ref "SV8") (pin "8") (pinfunction "8_8") (pintype "passive"))
      (node (ref "U1") (pin "11") (pinfunction "GND2_11") (pintype "power_in"))
      (node (ref "U1") (pin "8") (pinfunction "GND1_8") (pintype "power_in"))
      (node (ref "U2") (pin "13") (pinfunction "PGND2_13") (pintype "bidirectional"))
      (node (ref "U2") (pin "17") (pinfunction "PPAD_17") (pintype "bidirectional"))
      (node (ref "U2") (pin "4") (pinfunction "PGND1_4") (pintype "bidirectional"))
      (node (ref "U2") (pin "8") (pinfunction "GND_8") (pintype "bidirectional"))
      (node (ref "U3") (pin "GND1") (pinfunction "GND_GND1") (pintype "bidirectional"))
      (node (ref "X1") (pin "4") (pinfunction "4_4") (pintype "passive"))
      (node (ref "X2") (pin "3") (pinfunction "3_3") (pintype "input"))
      (node (ref "X2") (pin "6") (pinfunction "6_6") (pintype "input"))
      (node (ref "X2") (pin "COM_TERM") (pinfunction "COM_TERM_COM_TERM") (pintype "input"))
      (node (ref "X2") (pin "DETECT") (pinfunction "DETECT_DETECT") (pintype "input"))
      (node (ref "X2") (pin "WRITE_PROT") (pinfunction "WRITE_PROT_WRITE_PROT") (pintype "input"))
    )
    (net (code "69") (name "Net-(C6-Pad1)") (class "Default")
      (node (ref "C6") (pin "1") (pinfunction "1_1") (pintype "passive"))
      (node (ref "R5") (pin "1") (pinfunction "1_1") (pintype "passive"))
      (node (ref "S1") (pin "A1") (pinfunction "A1_A1") (pintype "passive"))
    )
    (net (code "70") (name "Net-(IC1A-OSC_IN)") (class "Default")
      (node (ref "C19") (pin "1") (pinfunction "1_1") (pintype "passive"))
      (node (ref "IC1") (pin "23") (pinfunction "OSC_IN_23") (pintype "bidirectional"))
      (node (ref "Q1") (pin "2") (pinfunction "2_2") (pintype "passive"))
      (node (ref "R11") (pin "2") (pinfunction "2_2") (pintype "passive"))
    )
    (net (code "71") (name "Net-(IC1A-OSC_OUT)") (class "Default")
      (node (ref "C20") (pin "1") (pinfunction "1_1") (pintype "passive"))
      (node (ref "IC1") (pin "24") (pinfunction "OSC_OUT_24") (pintype "bidirectional"))
      (node (ref "Q1") (pin "1") (pinfunction "1_1") (pintype "passive"))
      (node (ref "R11") (pin "1") (pinfunction "1_1") (pintype "passive"))
    )
    (net (code "72") (name "Net-(IC1A-PA11)") (class "Default")
      (node (ref "IC1") (pin "103") (pinfunction "PA11_103") (pintype "bidirectional"))
      (node (ref "U3") (pin "D-1") (pinfunction "D-_D-1") (pintype "bidirectional"))
    )
    (net (code "73") (name "Net-(IC1A-PA12)") (class "Default")
      (node (ref "IC1") (pin "104") (pinfunction "PA12_104") (pintype "bidirectional"))
      (node (ref "U3") (pin "D+1") (pinfunction "D+_D+1") (pintype "bidirectional"))
    )
    (net (code "74") (name "Net-(IC1A-PC14)") (class "Default")
      (node (ref "C29") (pin "1") (pinfunction "1_1") (pintype "passive"))
      (node (ref "IC1") (pin "8") (pinfunction "PC14_8") (pintype "bidirectional"))
      (node (ref "Q2") (pin "1") (pinfunction "1_1") (pintype "passive"))
    )
    (net (code "75") (name "Net-(IC1A-PC15)") (class "Default")
      (node (ref "C28") (pin "1") (pinfunction "1_1") (pintype "passive"))
      (node (ref "IC1") (pin "9") (pinfunction "PC15_9") (pintype "bidirectional"))
      (node (ref "Q2") (pin "2") (pinfunction "2_2") (pintype "passive"))
    )
    (net (code "76") (name "Net-(IC2A-AD0)") (class "Default")
      (node (ref "IC2") (pin "9") (pinfunction "AD0_9") (pintype "input"))
      (node (ref "R14") (pin "2") (pinfunction "2_2") (pintype "passive"))
      (node (ref "R26") (pin "2") (pinfunction "2_2") (pintype "passive"))
    )
    (net (code "77") (name "Net-(IC2A-CPOUT)") (class "Default")
      (node (ref "C33") (pin "1") (pinfunction "1_1") (pintype "passive"))
      (node (ref "IC2") (pin "20") (pinfunction "CPOUT_20") (pintype "output"))
    )
    (net (code "78") (name "Net-(IC2A-INT)") (class "Default")
      (node (ref "IC2") (pin "12") (pinfunction "INT_12") (pintype "open_collector"))
      (node (ref "R27") (pin "2") (pinfunction "2_2") (pintype "passive"))
    )
    (net (code "79") (name "Net-(IC2A-REGOUT)") (class "Default")
      (node (ref "C32") (pin "1") (pinfunction "1_1") (pintype "passive"))
      (node (ref "IC2") (pin "10") (pinfunction "REGOUT_10") (pintype "output"))
    )
    (net (code "80") (name "Net-(IC2A-SCL)") (class "Default")
      (node (ref "IC2") (pin "23") (pinfunction "SCL_23") (pintype "input"))
      (node (ref "R24") (pin "2") (pinfunction "2_2") (pintype "passive"))
    )
    (net (code "81") (name "Net-(IC2A-SDA)") (class "Default")
      (node (ref "IC2") (pin "24") (pinfunction "SDA_24") (pintype "bidirectional"))
      (node (ref "R25") (pin "2") (pinfunction "2_2") (pintype "passive"))
    )
    (net (code "82") (name "Net-(LED1-PadA)") (class "Default")
      (node (ref "LED1") (pin "A") (pinfunction "A_A") (pintype "passive"))
      (node (ref "R20") (pin "1") (pinfunction "1_1") (pintype "passive"))
    )
    (net (code "83") (name "Net-(LED2-PadA)") (class "Default")
      (node (ref "LED2") (pin "A") (pinfunction "A_A") (pintype "passive"))
      (node (ref "R21") (pin "1") (pinfunction "1_1") (pintype "passive"))
    )
    (net (code "84") (name "Net-(LED3-PadA)") (class "Default")
      (node (ref "LED3") (pin "A") (pinfunction "A_A") (pintype "passive"))
      (node (ref "R22") (pin "1") (pinfunction "1_1") (pintype "passive"))
    )
    (net (code "85") (name "Net-(LED4-PadA)") (class "Default")
      (node (ref "LED4") (pin "A") (pinfunction "A_A") (pintype "passive"))
      (node (ref "R23") (pin "1") (pinfunction "1_1") (pintype "passive"))
    )
    (net (code "86") (name "Net-(U1-ILIM)") (class "Default")
      (node (ref "R4") (pin "2") (pinfunction "2_2") (pintype "passive"))
      (node (ref "U1") (pin "5") (pinfunction "ILIM_5") (pintype "input"))
    )
    (net (code "87") (name "Net-(U1-PG)") (class "Default")
      (node (ref "R3") (pin "2") (pinfunction "2_2") (pintype "passive"))
      (node (ref "U1") (pin "4") (pinfunction "PG_4") (pintype "input"))
    )
    (net (code "88") (name "Net-(U1-PGFB)") (class "Default")
      (node (ref "R10") (pin "2") (pinfunction "2_2") (pintype "passive"))
      (node (ref "R9") (pin "1") (pinfunction "1_1") (pintype "passive"))
      (node (ref "U1") (pin "6") (pinfunction "PGFB_6") (pintype "bidirectional"))
    )
    (net (code "89") (name "Net-(U1-SET)") (class "Default")
      (node (ref "C13") (pin "1") (pinfunction "1_1") (pintype "passive"))
      (node (ref "R7") (pin "2") (pinfunction "2_2") (pintype "passive"))
      (node (ref "U1") (pin "7") (pinfunction "SET_7") (pintype "input"))
    )
    (net (code "90") (name "Net-(U2-SW1)") (class "Default")
      (node (ref "C5") (pin "1") (pinfunction "1_1") (pintype "passive"))
      (node (ref "L1") (pin "2") (pinfunction "2_2") (pintype "passive"))
      (node (ref "U2") (pin "3") (pinfunction "SW1_3") (pintype "bidirectional"))
    )
    (net (code "91") (name "Net-(U2-SW2)") (class "Default")
      (node (ref "C15") (pin "1") (pinfunction "1_1") (pintype "passive"))
      (node (ref "L2") (pin "1") (pinfunction "1_1") (pintype "passive"))
      (node (ref "U2") (pin "14") (pinfunction "SW2_14") (pintype "bidirectional"))
    )
    (net (code "92") (name "Net-(U2-VBST1)") (class "Default")
      (node (ref "C5") (pin "2") (pinfunction "2_2") (pintype "passive"))
      (node (ref "U2") (pin "2") (pinfunction "VBST1_2") (pintype "input"))
    )
    (net (code "93") (name "Net-(U2-VBST2)") (class "Default")
      (node (ref "C15") (pin "2") (pinfunction "2_2") (pintype "passive"))
      (node (ref "U2") (pin "15") (pinfunction "VBST2_15") (pintype "input"))
    )
    (net (code "94") (name "Net-(U2-VFB1)") (class "Default")
      (node (ref "R1") (pin "2") (pinfunction "2_2") (pintype "passive"))
      (node (ref "R2") (pin "1") (pinfunction "1_1") (pintype "passive"))
      (node (ref "U2") (pin "7") (pinfunction "VFB1_7") (pintype "input"))
    )
    (net (code "95") (name "Net-(U2-VFB2)") (class "Default")
      (node (ref "R6") (pin "2") (pinfunction "2_2") (pintype "passive"))
      (node (ref "R8") (pin "1") (pinfunction "1_1") (pintype "passive"))
      (node (ref "U2") (pin "10") (pinfunction "VFB2_10") (pintype "input"))
    )
    (net (code "96") (name "Net-(U2-VREG5)") (class "Default")
      (node (ref "C14") (pin "1") (pinfunction "1_1") (pintype "passive"))
      (node (ref "U2") (pin "9") (pinfunction "VREG5_9") (pintype "output"))
    )
    (net (code "97") (name "VCC") (class "Default")
      (node (ref "C26") (pin "1") (pinfunction "1_1") (pintype "passive"))
      (node (ref "C4") (pin "1") (pinfunction "1_1") (pintype "passive"))
      (node (ref "L2") (pin "2") (pinfunction "2_2") (pintype "passive"))
      (node (ref "R12") (pin "1") (pinfunction "1_1") (pintype "passive"))
      (node (ref "R13") (pin "1") (pinfunction "1_1") (pintype "passive"))
      (node (ref "R20") (pin "2") (pinfunction "2_2") (pintype "passive"))
      (node (ref "R21") (pin "2") (pinfunction "2_2") (pintype "passive"))
      (node (ref "R22") (pin "2") (pinfunction "2_2") (pintype "passive"))
      (node (ref "R23") (pin "2") (pinfunction "2_2") (pintype "passive"))
      (node (ref "R3") (pin "1") (pinfunction "1_1") (pintype "passive"))
      (node (ref "R8") (pin "2") (pinfunction "2_2") (pintype "passive"))
      (node (ref "SV3") (pin "1") (pinfunction "1_1") (pintype "passive"))
      (node (ref "SV3") (pin "11") (pinfunction "11_11") (pintype "passive"))
      (node (ref "SV3") (pin "13") (pinfunction "13_13") (pintype "passive"))
      (node (ref "SV3") (pin "15") (pinfunction "15_15") (pintype "passive"))
      (node (ref "SV3") (pin "3") (pinfunction "3_3") (pintype "passive"))
      (node (ref "SV3") (pin "5") (pinfunction "5_5") (pintype "passive"))
      (node (ref "SV3") (pin "7") (pinfunction "7_7") (pintype "passive"))
      (node (ref "SV3") (pin "9") (pinfunction "9_9") (pintype "passive"))
      (node (ref "SV7") (pin "10") (pinfunction "10_10") (pintype "passive"))
      (node (ref "SV7") (pin "3") (pinfunction "3_3") (pintype "passive"))
      (node (ref "SV7") (pin "4") (pinfunction "4_4") (pintype "passive"))
      (node (ref "SV7") (pin "9") (pinfunction "9_9") (pintype "passive"))
      (node (ref "SV8") (pin "10") (pinfunction "10_10") (pintype "passive"))
      (node (ref "SV8") (pin "3") (pinfunction "3_3") (pintype "passive"))
      (node (ref "SV8") (pin "4") (pinfunction "4_4") (pintype "passive"))
      (node (ref "SV8") (pin "9") (pinfunction "9_9") (pintype "passive"))
      (node (ref "U1") (pin "1") (pinfunction "IN1_1") (pintype "input"))
      (node (ref "U1") (pin "2") (pinfunction "IN2_2") (pintype "input"))
      (node (ref "U1") (pin "3") (pinfunction "EN/UV_3") (pintype "input"))
      (node (ref "U3") (pin "VBUS1") (pinfunction "VBUS_VBUS1") (pintype "bidirectional"))
      (node (ref "X1") (pin "1") (pinfunction "1_1") (pintype "passive"))
    )
    (net (code "98") (name "VDD") (class "Default")
      (node (ref "C10") (pin "1") (pinfunction "1_1") (pintype "passive"))
      (node (ref "C12") (pin "1") (pinfunction "1_1") (pintype "passive"))
      (node (ref "C16") (pin "1") (pinfunction "1_1") (pintype "passive"))
      (node (ref "C17") (pin "1") (pinfunction "1_1") (pintype "passive"))
      (node (ref "C18") (pin "1") (pinfunction "1_1") (pintype "passive"))
      (node (ref "C2") (pin "1") (pinfunction "1_1") (pintype "passive"))
      (node (ref "C21") (pin "1") (pinfunction "1_1") (pintype "passive"))
      (node (ref "C22") (pin "1") (pinfunction "1_1") (pintype "passive"))
      (node (ref "C23") (pin "1") (pinfunction "1_1") (pintype "passive"))
      (node (ref "C25") (pin "1") (pinfunction "1_1") (pintype "passive"))
      (node (ref "C27") (pin "1") (pinfunction "1_1") (pintype "passive"))
      (node (ref "C30") (pin "1") (pinfunction "1_1") (pintype "passive"))
      (node (ref "C31") (pin "1") (pinfunction "1_1") (pintype "passive"))
      (node (ref "C7") (pin "1") (pinfunction "1_1") (pintype "passive"))
      (node (ref "C8") (pin "1") (pinfunction "1_1") (pintype "passive"))
      (node (ref "C9") (pin "1") (pinfunction "1_1") (pintype "passive"))
      (node (ref "IC1") (pin "108") (pinfunction "VDD_108") (pintype "power_in"))
      (node (ref "IC1") (pin "121") (pinfunction "VDD_121") (pintype "power_in"))
      (node (ref "IC1") (pin "131") (pinfunction "VDD_131") (pintype "power_in"))
      (node (ref "IC1") (pin "144") (pinfunction "VDD_144") (pintype "power_in"))
      (node (ref "IC1") (pin "17") (pinfunction "VDD_17") (pintype "power_in"))
      (node (ref "IC1") (pin "32") (pinfunction "VREF+_32") (pintype "power_in"))
      (node (ref "IC1") (pin "33") (pinfunction "VDDA_33") (pintype "power_in"))
      (node (ref "IC1") (pin "39") (pinfunction "VDD_39") (pintype "power_in"))
      (node (ref "IC1") (pin "52") (pinfunction "VDD_52") (pintype "power_in"))
      (node (ref "IC1") (pin "6") (pinfunction "VBAT_6") (pintype "power_in"))
      (node (ref "IC1") (pin "62") (pinfunction "VDD_62") (pintype "power_in"))
      (node (ref "IC1") (pin "72") (pinfunction "VDD_72") (pintype "power_in"))
      (node (ref "IC1") (pin "84") (pinfunction "VDD_84") (pintype "power_in"))
      (node (ref "IC1") (pin "95") (pinfunction "VDD_95") (pintype "power_in"))
      (node (ref "L1") (pin "1") (pinfunction "1_1") (pintype "passive"))
      (node (ref "R1") (pin "1") (pinfunction "1_1") (pintype "passive"))
      (node (ref "R15") (pin "1") (pinfunction "1_1") (pintype "passive"))
      (node (ref "R16") (pin "1") (pinfunction "1_1") (pintype "passive"))
      (node (ref "R17") (pin "1") (pinfunction "1_1") (pintype "passive"))
      (node (ref "R19") (pin "1") (pinfunction "1_1") (pintype "passive"))
      (node (ref "R28") (pin "1") (pinfunction "1_1") (pintype "passive"))
      (node (ref "R29") (pin "1") (pinfunction "1_1") (pintype "passive"))
      (node (ref "R30") (pin "1") (pinfunction "1_1") (pintype "passive"))
      (node (ref "R31") (pin "1") (pinfunction "1_1") (pintype "passive"))
      (node (ref "R32") (pin "1") (pinfunction "1_1") (pintype "passive"))
      (node (ref "R5") (pin "2") (pinfunction "2_2") (pintype "passive"))
      (node (ref "SV1") (pin "6") (pinfunction "6_6") (pintype "passive"))
      (node (ref "SV2") (pin "6") (pinfunction "6_6") (pintype "passive"))
      (node (ref "SV6") (pin "1") (pinfunction "1_1") (pintype "passive"))
      (node (ref "SV6") (pin "2") (pinfunction "2_2") (pintype "passive"))
      (node (ref "X2") (pin "4") (pinfunction "4_4") (pintype "input"))
    )
    (net (code "99") (name "VEE") (class "Default")
      (node (ref "C11") (pin "1") (pinfunction "1_1") (pintype "passive"))
      (node (ref "C34") (pin "1") (pinfunction "1_1") (pintype "passive"))
      (node (ref "IC2") (pin "13") (pinfunction "VDD_13") (pintype "power_in"))
      (node (ref "IC2") (pin "8") (pinfunction "VLOGIC_8") (pintype "power_in"))
      (node (ref "R9") (pin "2") (pinfunction "2_2") (pintype "passive"))
      (node (ref "U1") (pin "10") (pinfunction "OUT_10") (pintype "power_in"))
      (node (ref "U1") (pin "9") (pinfunction "OUTS_9") (pintype "input"))
    )
    (net (code "100") (name "unconnected-(IC1A-PA0-Pad34)") (class "Default")
      (node (ref "IC1") (pin "34") (pinfunction "PA0_34") (pintype "bidirectional"))
    )
    (net (code "101") (name "unconnected-(IC1A-PA1-Pad35)") (class "Default")
      (node (ref "IC1") (pin "35") (pinfunction "PA1_35") (pintype "bidirectional"))
    )
    (net (code "102") (name "unconnected-(IC1A-PA2-Pad36)") (class "Default")
      (node (ref "IC1") (pin "36") (pinfunction "PA2_36") (pintype "bidirectional"))
    )
    (net (code "103") (name "unconnected-(IC1A-PA3-Pad37)") (class "Default")
      (node (ref "IC1") (pin "37") (pinfunction "PA3_37") (pintype "bidirectional"))
    )
    (net (code "104") (name "unconnected-(IC1A-PA4-Pad40)") (class "Default")
      (node (ref "IC1") (pin "40") (pinfunction "PA4_40") (pintype "bidirectional"))
    )
    (net (code "105") (name "unconnected-(IC1A-PB2-Pad48)") (class "Default")
      (node (ref "IC1") (pin "48") (pinfunction "PB2_48") (pintype "bidirectional"))
    )
    (net (code "106") (name "unconnected-(IC1A-PB9-Pad140)") (class "Default")
      (node (ref "IC1") (pin "140") (pinfunction "PB9_140") (pintype "bidirectional"))
    )
    (net (code "107") (name "unconnected-(IC1A-PB12-Pad73)") (class "Default")
      (node (ref "IC1") (pin "73") (pinfunction "PB12_73") (pintype "bidirectional"))
    )
    (net (code "108") (name "unconnected-(IC1A-PB13-Pad74)") (class "Default")
      (node (ref "IC1") (pin "74") (pinfunction "PB13_74") (pintype "bidirectional"))
    )
    (net (code "109") (name "unconnected-(IC1A-PB14-Pad75)") (class "Default")
      (node (ref "IC1") (pin "75") (pinfunction "PB14_75") (pintype "bidirectional"))
    )
    (net (code "110") (name "unconnected-(IC1A-PB15-Pad76)") (class "Default")
      (node (ref "IC1") (pin "76") (pinfunction "PB15_76") (pintype "bidirectional"))
    )
    (net (code "111") (name "unconnected-(IC1A-PC0-Pad26)") (class "Default")
      (node (ref "IC1") (pin "26") (pinfunction "PC0_26") (pintype "bidirectional"))
    )
    (net (code "112") (name "unconnected-(IC1A-PC1-Pad27)") (class "Default")
      (node (ref "IC1") (pin "27") (pinfunction "PC1_27") (pintype "bidirectional"))
    )
    (net (code "113") (name "unconnected-(IC1A-PC2-Pad28)") (class "Default")
      (node (ref "IC1") (pin "28") (pinfunction "PC2_28") (pintype "bidirectional"))
    )
    (net (code "114") (name "unconnected-(IC1A-PC3-Pad29)") (class "Default")
      (node (ref "IC1") (pin "29") (pinfunction "PC3_29") (pintype "bidirectional"))
    )
    (net (code "115") (name "unconnected-(IC1A-PC4-Pad44)") (class "Default")
      (node (ref "IC1") (pin "44") (pinfunction "PC4_44") (pintype "bidirectional"))
    )
    (net (code "116") (name "unconnected-(IC1A-PC5-Pad45)") (class "Default")
      (node (ref "IC1") (pin "45") (pinfunction "PC5_45") (pintype "bidirectional"))
    )
    (net (code "117") (name "unconnected-(IC1A-PC6-Pad96)") (class "Default")
      (node (ref "IC1") (pin "96") (pinfunction "PC6_96") (pintype "bidirectional"))
    )
    (net (code "118") (name "unconnected-(IC1A-PC7-Pad97)") (class "Default")
      (node (ref "IC1") (pin "97") (pinfunction "PC7_97") (pintype "bidirectional"))
    )
    (net (code "119") (name "unconnected-(IC1A-PD0-Pad114)") (class "Default")
      (node (ref "IC1") (pin "114") (pinfunction "PD0_114") (pintype "bidirectional"))
    )
    (net (code "120") (name "unconnected-(IC1A-PD1-Pad115)") (class "Default")
      (node (ref "IC1") (pin "115") (pinfunction "PD1_115") (pintype "bidirectional"))
    )
    (net (code "121") (name "unconnected-(IC1A-PD3-Pad117)") (class "Default")
      (node (ref "IC1") (pin "117") (pinfunction "PD3_117") (pintype "bidirectional"))
    )
    (net (code "122") (name "unconnected-(IC1A-PD4-Pad118)") (class "Default")
      (node (ref "IC1") (pin "118") (pinfunction "PD4_118") (pintype "bidirectional"))
    )
    (net (code "123") (name "unconnected-(IC1A-PD5-Pad119)") (class "Default")
      (node (ref "IC1") (pin "119") (pinfunction "PD5_119") (pintype "bidirectional"))
    )
    (net (code "124") (name "unconnected-(IC1A-PD6-Pad122)") (class "Default")
      (node (ref "IC1") (pin "122") (pinfunction "PD6_122") (pintype "bidirectional"))
    )
    (net (code "125") (name "unconnected-(IC1A-PD7-Pad123)") (class "Default")
      (node (ref "IC1") (pin "123") (pinfunction "PD7_123") (pintype "bidirectional"))
    )
    (net (code "126") (name "unconnected-(IC1A-PD8-Pad77)") (class "Default")
      (node (ref "IC1") (pin "77") (pinfunction "PD8_77") (pintype "bidirectional"))
    )
    (net (code "127") (name "unconnected-(IC1A-PD9-Pad78)") (class "Default")
      (node (ref "IC1") (pin "78") (pinfunction "PD9_78") (pintype "bidirectional"))
    )
    (net (code "128") (name "unconnected-(IC1A-PD10-Pad79)") (class "Default")
      (node (ref "IC1") (pin "79") (pinfunction "PD10_79") (pintype "bidirectional"))
    )
    (net (code "129") (name "unconnected-(IC1A-PD11-Pad80)") (class "Default")
      (node (ref "IC1") (pin "80") (pinfunction "PD11_80") (pintype "bidirectional"))
    )
    (net (code "130") (name "unconnected-(IC1A-PE0-Pad141)") (class "Default")
      (node (ref "IC1") (pin "141") (pinfunction "PE0_141") (pintype "bidirectional"))
    )
    (net (code "131") (name "unconnected-(IC1A-PE1-Pad142)") (class "Default")
      (node (ref "IC1") (pin "142") (pinfunction "PE1_142") (pintype "bidirectional"))
    )
    (net (code "132") (name "unconnected-(IC1A-PE2-Pad1)") (class "Default")
      (node (ref "IC1") (pin "1") (pinfunction "PE2_1") (pintype "bidirectional"))
    )
    (net (code "133") (name "unconnected-(IC1A-PE3-Pad2)") (class "Default")
      (node (ref "IC1") (pin "2") (pinfunction "PE3_2") (pintype "bidirectional"))
    )
    (net (code "134") (name "unconnected-(IC1A-PE7-Pad58)") (class "Default")
      (node (ref "IC1") (pin "58") (pinfunction "PE7_58") (pintype "bidirectional"))
    )
    (net (code "135") (name "unconnected-(IC1A-PE8-Pad59)") (class "Default")
      (node (ref "IC1") (pin "59") (pinfunction "PE8_59") (pintype "bidirectional"))
    )
    (net (code "136") (name "unconnected-(IC1A-PE9-Pad60)") (class "Default")
      (node (ref "IC1") (pin "60") (pinfunction "PE9_60") (pintype "bidirectional"))
    )
    (net (code "137") (name "unconnected-(IC1A-PE10-Pad63)") (class "Default")
      (node (ref "IC1") (pin "63") (pinfunction "PE10_63") (pintype "bidirectional"))
    )
    (net (code "138") (name "unconnected-(IC1A-PE11-Pad64)") (class "Default")
      (node (ref "IC1") (pin "64") (pinfunction "PE11_64") (pintype "bidirectional"))
    )
    (net (code "139") (name "unconnected-(IC1A-PE12-Pad65)") (class "Default")
      (node (ref "IC1") (pin "65") (pinfunction "PE12_65") (pintype "bidirectional"))
    )
    (net (code "140") (name "unconnected-(IC1A-PE13-Pad66)") (class "Default")
      (node (ref "IC1") (pin "66") (pinfunction "PE13_66") (pintype "bidirectional"))
    )
    (net (code "141") (name "unconnected-(IC1A-PE14-Pad67)") (class "Default")
      (node (ref "IC1") (pin "67") (pinfunction "PE14_67") (pintype "bidirectional"))
    )
    (net (code "142") (name "unconnected-(IC1A-PE15-Pad68)") (class "Default")
      (node (ref "IC1") (pin "68") (pinfunction "PE15_68") (pintype "bidirectional"))
    )
    (net (code "143") (name "unconnected-(IC2A-AUX_CL-Pad7)") (class "Default")
      (node (ref "IC2") (pin "7") (pinfunction "AUX_CL_7") (pintype "bidirectional"))
    )
    (net (code "144") (name "unconnected-(IC2A-AUX_DA-Pad6)") (class "Default")
      (node (ref "IC2") (pin "6") (pinfunction "AUX_DA_6") (pintype "bidirectional"))
    )
    (net (code "145") (name "unconnected-(IC2A-RESV-Pad19)") (class "Default")
      (node (ref "IC2") (pin "19") (pinfunction "RESV_19") (pintype "passive"))
    )
    (net (code "146") (name "unconnected-(IC2A-RESV-Pad21)") (class "Default")
      (node (ref "IC2") (pin "21") (pinfunction "RESV_21") (pintype "passive"))
    )
    (net (code "147") (name "unconnected-(IC2A-RESV-Pad22)") (class "Default")
      (node (ref "IC2") (pin "22") (pinfunction "RESV_22") (pintype "passive"))
    )
    (net (code "148") (name "unconnected-(IC2B-NC-Pad2)") (class "Default")
      (node (ref "IC2") (pin "2") (pinfunction "NC_2") (pintype "no_connect"))
    )
    (net (code "149") (name "unconnected-(IC2B-NC-Pad3)") (class "Default")
      (node (ref "IC2") (pin "3") (pinfunction "NC_3") (pintype "no_connect"))
    )
    (net (code "150") (name "unconnected-(IC2B-NC-Pad4)") (class "Default")
      (node (ref "IC2") (pin "4") (pinfunction "NC_4") (pintype "no_connect"))
    )
    (net (code "151") (name "unconnected-(IC2B-NC-Pad5)") (class "Default")
      (node (ref "IC2") (pin "5") (pinfunction "NC_5") (pintype "no_connect"))
    )
    (net (code "152") (name "unconnected-(IC2B-NC-Pad14)") (class "Default")
      (node (ref "IC2") (pin "14") (pinfunction "NC_14") (pintype "no_connect"))
    )
    (net (code "153") (name "unconnected-(IC2B-NC-Pad15)") (class "Default")
      (node (ref "IC2") (pin "15") (pinfunction "NC_15") (pintype "no_connect"))
    )
    (net (code "154") (name "unconnected-(IC2B-NC-Pad16)") (class "Default")
      (node (ref "IC2") (pin "16") (pinfunction "NC_16") (pintype "no_connect"))
    )
    (net (code "155") (name "unconnected-(IC2B-NC-Pad17)") (class "Default")
      (node (ref "IC2") (pin "17") (pinfunction "NC_17") (pintype "no_connect"))
    )
    (net (code "156") (name "unconnected-(SV6-Pad11)") (class "Default")
      (node (ref "SV6") (pin "11") (pinfunction "11_11") (pintype "passive"))
    )
    (net (code "157") (name "unconnected-(SV6-Pad17)") (class "Default")
      (node (ref "SV6") (pin "17") (pinfunction "17_17") (pintype "passive"))
    )
    (net (code "158") (name "unconnected-(SV6-Pad19)") (class "Default")
      (node (ref "SV6") (pin "19") (pinfunction "19_19") (pintype "passive"))
    )
    (net (code "159") (name "unconnected-(U2-PG1-Pad6)") (class "Default")
      (node (ref "U2") (pin "6") (pinfunction "PG1_6") (pintype "output"))
    )
    (net (code "160") (name "unconnected-(U2-PG2-Pad11)") (class "Default")
      (node (ref "U2") (pin "11") (pinfunction "PG2_11") (pintype "output"))
    )
    (net (code "161") (name "unconnected-(U3-USBID-PadID1)") (class "Default")
      (node (ref "U3") (pin "ID1") (pinfunction "USBID_ID1") (pintype "bidirectional"))
    )
    (net (code "162") (name "unconnected-(X1-Pad2)") (class "Default")
      (node (ref "X1") (pin "2") (pinfunction "2_2") (pintype "passive"))
    )
    (net (code "163") (name "unconnected-(X1-Pad3)") (class "Default")
      (node (ref "X1") (pin "3") (pinfunction "3_3") (pintype "passive"))
    )
  )
)
